# Indome_Ekow_Annan_3031820.net
KiCad netlist of a schematic drawn in EAGLE
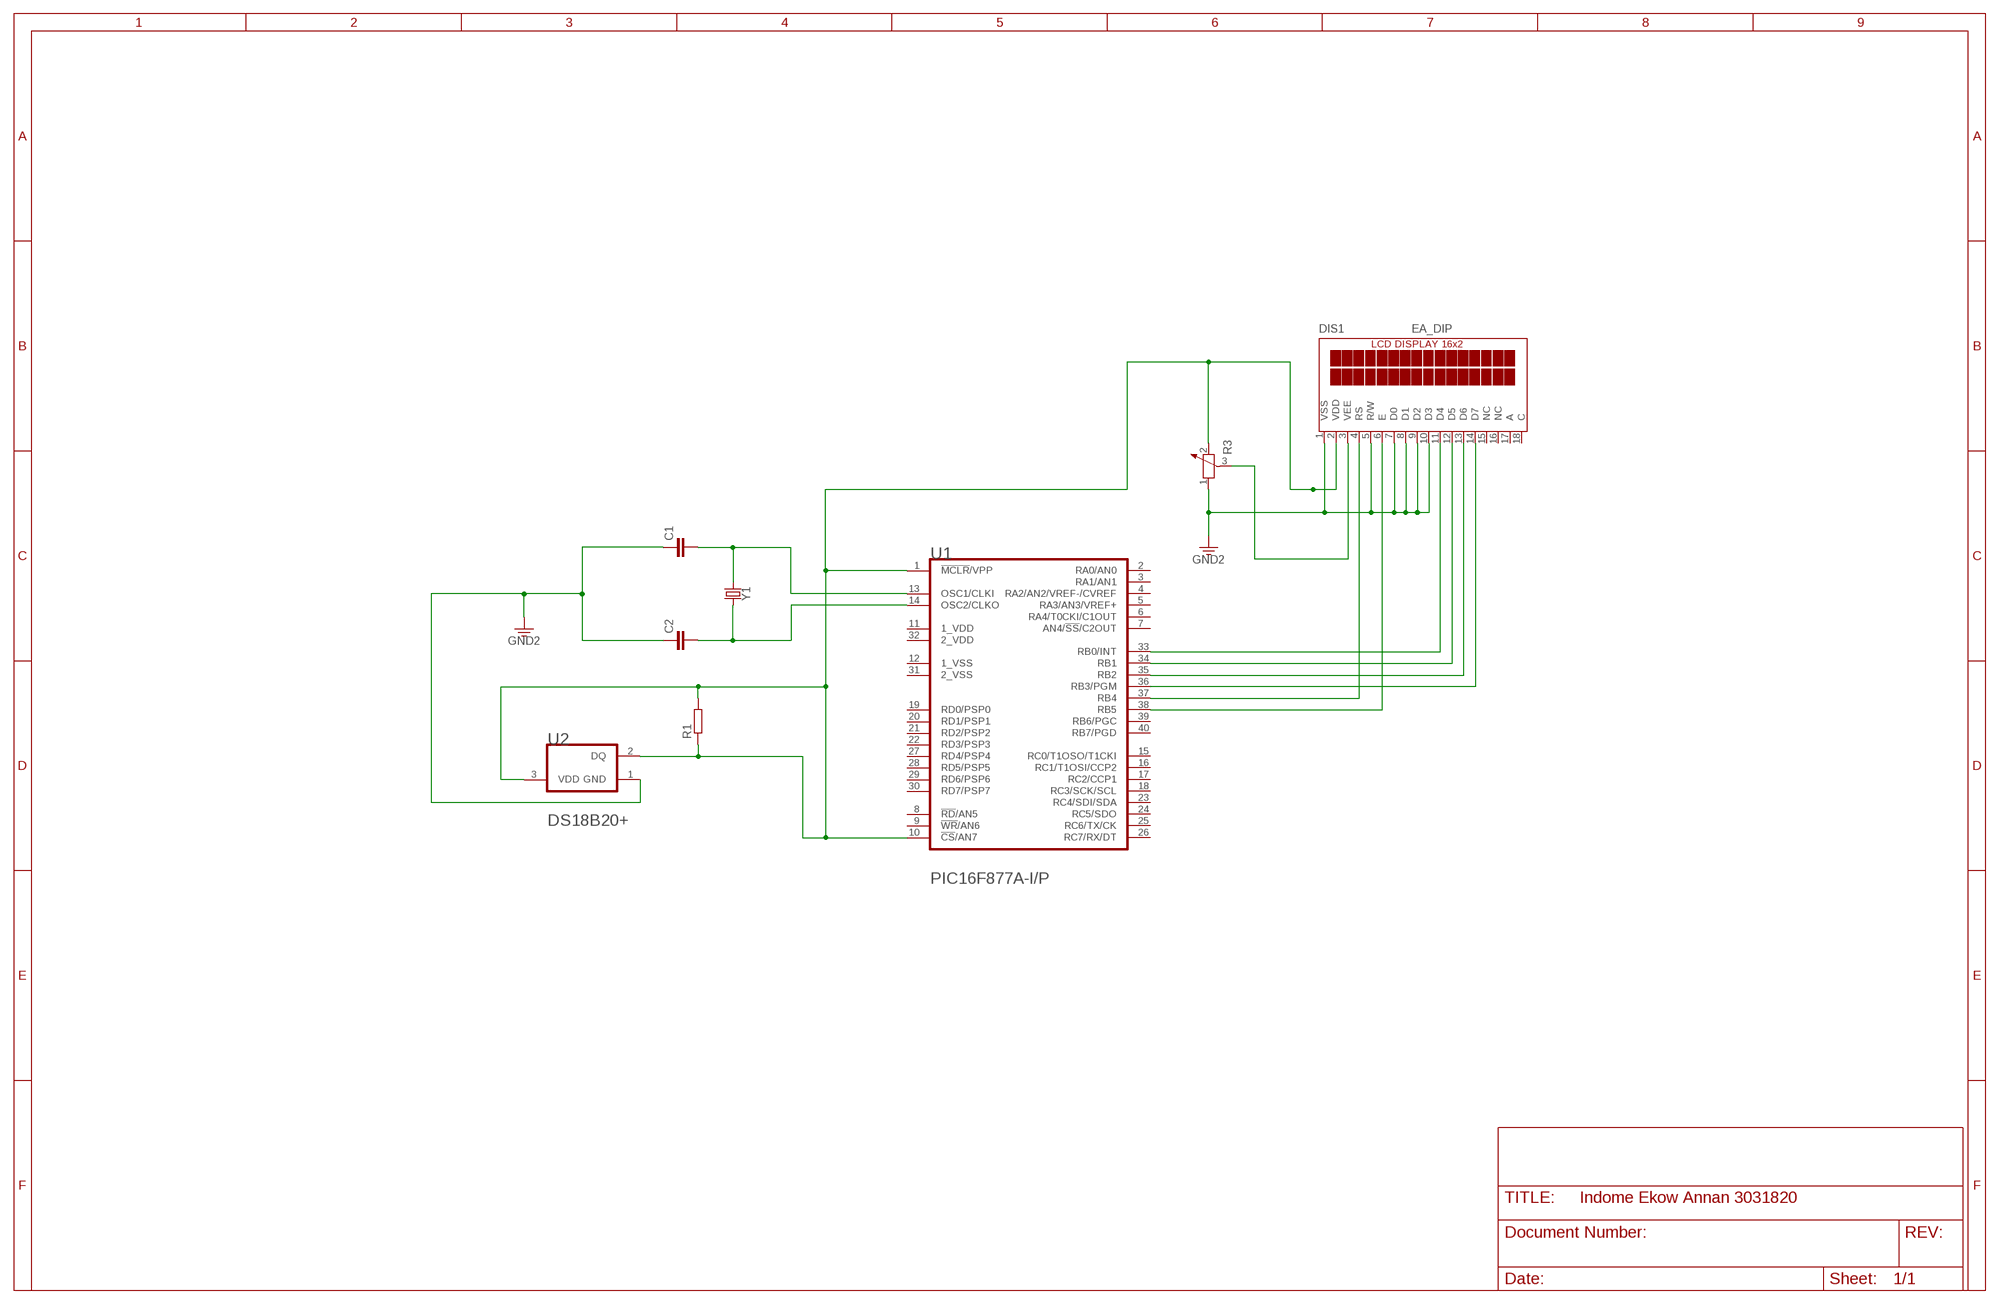
[diagram p0: schematic, sheet 1]

(export (version "E")
  (design (tool "Eeschema 10.0.6"))
  (components
    (comp (ref "C1")
      (value "C2,5-3")
      (footprint "eagle-import:C2.5-3")
      (libsource (lib "eagle-import") (part "C2,5-3"))
    )
    (comp (ref "C2")
      (value "C2,5-3")
      (footprint "eagle-import:C2.5-3")
      (libsource (lib "eagle-import") (part "C2,5-3"))
    )
    (comp (ref "DIS1")
      (value "EA_DIP")
      (footprint "eagle-import:EA_DIP")
      (libsource (lib "eagle-import") (part "EA_DIP"))
    )
    (comp (ref "R1")
      (value "R-EU_0204/2V")
      (footprint "eagle-import:0204V")
      (libsource (lib "eagle-import") (part "R-EU_0204/2V"))
    )
    (comp (ref "R3")
      (value "POTENTIOMETER_PT-10")
      (footprint "eagle-import:PT-10")
      (libsource (lib "eagle-import") (part "POTENTIOMETER_PT-10"))
    )
    (comp (ref "U1")
      (value "MICROCHIP_PIC16F877A-I-PMICROCHIP_PIC16F877A-I-P_0_0")
      (footprint "eagle-import:MICROCHIP_PIC16F877A-I-P_0")
      (fields (field (name "MF") "Microchip") (field (name "MPN") "PIC16F877A-I/P"))
      (libsource (lib "eagle-import") (part "MICROCHIP_PIC16F877A-I-PMICROCHIP_PIC16F877A-I-P_0_0"))
    )
    (comp (ref "U2")
      (value "MAXIM_DS18B20+MAXIM_DS18B20+_0_0")
      (footprint "eagle-import:MAXIM_DS18B20+_0")
      (fields (field (name "MF") "Maxim") (field (name "MPN") "DS18B20+"))
      (libsource (lib "eagle-import") (part "MAXIM_DS18B20+MAXIM_DS18B20+_0_0"))
    )
    (comp (ref "Y1")
      (value "CRYSTALPTH-2X6")
      (footprint "eagle-import:CRYSTAL-PTH-2X6-CYL")
      (libsource (lib "eagle-import") (part "CRYSTALPTH-2X6"))
    )
  )
  (nets
    (net (code "1") (name "/1_VDD") (class "Default")
      (node (ref "U1") (pin "11") (pinfunction "1_VDD_11") (pintype "power_in"))
    )
    (net (code "2") (name "/1_VSS") (class "Default")
      (node (ref "U1") (pin "12") (pinfunction "1_VSS_12") (pintype "power_in"))
    )
    (net (code "3") (name "/2_VDD") (class "Default")
      (node (ref "U1") (pin "32") (pinfunction "2_VDD_32") (pintype "power_in"))
    )
    (net (code "4") (name "/2_VSS") (class "Default")
      (node (ref "U1") (pin "31") (pinfunction "2_VSS_31") (pintype "power_in"))
    )
    (net (code "5") (name "GND2") (class "Default")
      (node (ref "C1") (pin "1") (pinfunction "1_1") (pintype "passive"))
      (node (ref "C2") (pin "1") (pinfunction "1_1") (pintype "passive"))
      (node (ref "DIS1") (pin "1") (pinfunction "VSS_1") (pintype "power_in"))
      (node (ref "DIS1") (pin "10") (pinfunction "D3_10") (pintype "input"))
      (node (ref "DIS1") (pin "5") (pinfunction "R/W_5") (pintype "input"))
      (node (ref "DIS1") (pin "7") (pinfunction "D0_7") (pintype "input"))
      (node (ref "DIS1") (pin "8") (pinfunction "D1_8") (pintype "input"))
      (node (ref "DIS1") (pin "9") (pinfunction "D2_9") (pintype "input"))
      (node (ref "R3") (pin "1") (pinfunction "1_1") (pintype "passive"))
      (node (ref "U2") (pin "1") (pinfunction "GND_1") (pintype "bidirectional"))
    )
    (net (code "6") (name "Net-(DIS1-D4)") (class "Default")
      (node (ref "DIS1") (pin "11") (pinfunction "D4_11") (pintype "input"))
      (node (ref "U1") (pin "33") (pinfunction "RB0/INT_33") (pintype "bidirectional"))
    )
    (net (code "7") (name "Net-(DIS1-D5)") (class "Default")
      (node (ref "DIS1") (pin "12") (pinfunction "D5_12") (pintype "input"))
      (node (ref "U1") (pin "34") (pinfunction "RB1_34") (pintype "bidirectional"))
    )
    (net (code "8") (name "Net-(DIS1-D6)") (class "Default")
      (node (ref "DIS1") (pin "13") (pinfunction "D6_13") (pintype "input"))
      (node (ref "U1") (pin "35") (pinfunction "RB2_35") (pintype "bidirectional"))
    )
    (net (code "9") (name "Net-(DIS1-D7)") (class "Default")
      (node (ref "DIS1") (pin "14") (pinfunction "D7_14") (pintype "input"))
      (node (ref "U1") (pin "36") (pinfunction "RB3/PGM_36") (pintype "bidirectional"))
    )
    (net (code "10") (name "Net-(DIS1-E)") (class "Default")
      (node (ref "DIS1") (pin "6") (pinfunction "E_6") (pintype "input"))
      (node (ref "U1") (pin "38") (pinfunction "RB5_38") (pintype "bidirectional"))
    )
    (net (code "11") (name "Net-(DIS1-RS)") (class "Default")
      (node (ref "DIS1") (pin "4") (pinfunction "RS_4") (pintype "input"))
      (node (ref "U1") (pin "37") (pinfunction "RB4_37") (pintype "bidirectional"))
    )
    (net (code "12") (name "Net-(DIS1-VDD)") (class "Default")
      (node (ref "DIS1") (pin "2") (pinfunction "VDD_2") (pintype "power_in"))
      (node (ref "R1") (pin "1") (pinfunction "1_1") (pintype "passive"))
      (node (ref "R1") (pin "2") (pinfunction "2_2") (pintype "passive"))
      (node (ref "R3") (pin "2") (pinfunction "2_2") (pintype "passive"))
      (node (ref "U1") (pin "1") (pinfunction "~{MCLR}/VPP_1") (pintype "input"))
      (node (ref "U1") (pin "10") (pinfunction "~{CS}/AN7_10") (pintype "bidirectional"))
      (node (ref "U2") (pin "2") (pinfunction "DQ_2") (pintype "bidirectional"))
      (node (ref "U2") (pin "3") (pinfunction "VDD_3") (pintype "bidirectional"))
    )
    (net (code "13") (name "Net-(DIS1-VEE)") (class "Default")
      (node (ref "DIS1") (pin "3") (pinfunction "VEE_3") (pintype "power_in"))
      (node (ref "R3") (pin "3") (pinfunction "3_3") (pintype "passive"))
    )
    (net (code "14") (name "Net-(U1-OSC1{slash}CLKI)") (class "Default")
      (node (ref "C1") (pin "2") (pinfunction "2_2") (pintype "passive"))
      (node (ref "U1") (pin "13") (pinfunction "OSC1/CLKI_13") (pintype "input"))
      (node (ref "Y1") (pin "1") (pinfunction "1_1") (pintype "passive"))
    )
    (net (code "15") (name "Net-(U1-OSC2{slash}CLKO)") (class "Default")
      (node (ref "C2") (pin "2") (pinfunction "2_2") (pintype "passive"))
      (node (ref "U1") (pin "14") (pinfunction "OSC2/CLKO_14") (pintype "output"))
      (node (ref "Y1") (pin "2") (pinfunction "2_2") (pintype "passive"))
    )
    (net (code "16") (name "unconnected-(DIS1-A-Pad17)") (class "Default")
      (node (ref "DIS1") (pin "17") (pinfunction "A_17") (pintype "passive"))
    )
    (net (code "17") (name "unconnected-(DIS1-C-Pad18)") (class "Default")
      (node (ref "DIS1") (pin "18") (pinfunction "C_18") (pintype "passive"))
    )
    (net (code "18") (name "unconnected-(DIS1-NC-Pad15)") (class "Default")
      (node (ref "DIS1") (pin "15") (pinfunction "NC_15") (pintype "no_connect"))
    )
    (net (code "19") (name "unconnected-(DIS1-NC-Pad16)") (class "Default")
      (node (ref "DIS1") (pin "16") (pinfunction "NC_16") (pintype "no_connect"))
    )
    (net (code "20") (name "unconnected-(U1-AN4{slash}~{SS}{slash}C2OUT-Pad7)") (class "Default")
      (node (ref "U1") (pin "7") (pinfunction "AN4/~{SS}/C2OUT_7") (pintype "bidirectional"))
    )
    (net (code "21") (name "unconnected-(U1-RA0{slash}AN0-Pad2)") (class "Default")
      (node (ref "U1") (pin "2") (pinfunction "RA0/AN0_2") (pintype "bidirectional"))
    )
    (net (code "22") (name "unconnected-(U1-RA1{slash}AN1-Pad3)") (class "Default")
      (node (ref "U1") (pin "3") (pinfunction "RA1/AN1_3") (pintype "bidirectional"))
    )
    (net (code "23") (name "unconnected-(U1-RA2{slash}AN2{slash}VREF-{slash}CVREF-Pad4)") (class "Default")
      (node (ref "U1") (pin "4") (pinfunction "RA2/AN2/VREF-/CVREF_4") (pintype "bidirectional"))
    )
    (net (code "24") (name "unconnected-(U1-RA3{slash}AN3{slash}VREF+-Pad5)") (class "Default")
      (node (ref "U1") (pin "5") (pinfunction "RA3/AN3/VREF+_5") (pintype "bidirectional"))
    )
    (net (code "25") (name "unconnected-(U1-RA4{slash}T0CKI{slash}C1OUT-Pad6)") (class "Default")
      (node (ref "U1") (pin "6") (pinfunction "RA4/T0CKI/C1OUT_6") (pintype "bidirectional"))
    )
    (net (code "26") (name "unconnected-(U1-RB6{slash}PGC-Pad39)") (class "Default")
      (node (ref "U1") (pin "39") (pinfunction "RB6/PGC_39") (pintype "bidirectional"))
    )
    (net (code "27") (name "unconnected-(U1-RB7{slash}PGD-Pad40)") (class "Default")
      (node (ref "U1") (pin "40") (pinfunction "RB7/PGD_40") (pintype "bidirectional"))
    )
    (net (code "28") (name "unconnected-(U1-RC0{slash}T1OSO{slash}T1CKI-Pad15)") (class "Default")
      (node (ref "U1") (pin "15") (pinfunction "RC0/T1OSO/T1CKI_15") (pintype "bidirectional"))
    )
    (net (code "29") (name "unconnected-(U1-RC1{slash}T1OSI{slash}CCP2-Pad16)") (class "Default")
      (node (ref "U1") (pin "16") (pinfunction "RC1/T1OSI/CCP2_16") (pintype "bidirectional"))
    )
    (net (code "30") (name "unconnected-(U1-RC2{slash}CCP1-Pad17)") (class "Default")
      (node (ref "U1") (pin "17") (pinfunction "RC2/CCP1_17") (pintype "bidirectional"))
    )
    (net (code "31") (name "unconnected-(U1-RC3{slash}SCK{slash}SCL-Pad18)") (class "Default")
      (node (ref "U1") (pin "18") (pinfunction "RC3/SCK/SCL_18") (pintype "bidirectional"))
    )
    (net (code "32") (name "unconnected-(U1-RC4{slash}SDI{slash}SDA-Pad23)") (class "Default")
      (node (ref "U1") (pin "23") (pinfunction "RC4/SDI/SDA_23") (pintype "bidirectional"))
    )
    (net (code "33") (name "unconnected-(U1-RC5{slash}SDO-Pad24)") (class "Default")
      (node (ref "U1") (pin "24") (pinfunction "RC5/SDO_24") (pintype "bidirectional"))
    )
    (net (code "34") (name "unconnected-(U1-RC6{slash}TX{slash}CK-Pad25)") (class "Default")
      (node (ref "U1") (pin "25") (pinfunction "RC6/TX/CK_25") (pintype "bidirectional"))
    )
    (net (code "35") (name "unconnected-(U1-RC7{slash}RX{slash}DT-Pad26)") (class "Default")
      (node (ref "U1") (pin "26") (pinfunction "RC7/RX/DT_26") (pintype "bidirectional"))
    )
    (net (code "36") (name "unconnected-(U1-RD0{slash}PSP0-Pad19)") (class "Default")
      (node (ref "U1") (pin "19") (pinfunction "RD0/PSP0_19") (pintype "bidirectional"))
    )
    (net (code "37") (name "unconnected-(U1-RD1{slash}PSP1-Pad20)") (class "Default")
      (node (ref "U1") (pin "20") (pinfunction "RD1/PSP1_20") (pintype "bidirectional"))
    )
    (net (code "38") (name "unconnected-(U1-RD2{slash}PSP2-Pad21)") (class "Default")
      (node (ref "U1") (pin "21") (pinfunction "RD2/PSP2_21") (pintype "bidirectional"))
    )
    (net (code "39") (name "unconnected-(U1-RD3{slash}PSP3-Pad22)") (class "Default")
      (node (ref "U1") (pin "22") (pinfunction "RD3/PSP3_22") (pintype "bidirectional"))
    )
    (net (code "40") (name "unconnected-(U1-RD4{slash}PSP4-Pad27)") (class "Default")
      (node (ref "U1") (pin "27") (pinfunction "RD4/PSP4_27") (pintype "bidirectional"))
    )
    (net (code "41") (name "unconnected-(U1-RD5{slash}PSP5-Pad28)") (class "Default")
      (node (ref "U1") (pin "28") (pinfunction "RD5/PSP5_28") (pintype "bidirectional"))
    )
    (net (code "42") (name "unconnected-(U1-RD6{slash}PSP6-Pad29)") (class "Default")
      (node (ref "U1") (pin "29") (pinfunction "RD6/PSP6_29") (pintype "bidirectional"))
    )
    (net (code "43") (name "unconnected-(U1-RD7{slash}PSP7-Pad30)") (class "Default")
      (node (ref "U1") (pin "30") (pinfunction "RD7/PSP7_30") (pintype "bidirectional"))
    )
    (net (code "44") (name "unconnected-(U1-~{RD}{slash}AN5-Pad8)") (class "Default")
      (node (ref "U1") (pin "8") (pinfunction "~{RD}/AN5_8") (pintype "bidirectional"))
    )
    (net (code "45") (name "unconnected-(U1-~{WR}{slash}AN6-Pad9)") (class "Default")
      (node (ref "U1") (pin "9") (pinfunction "~{WR}/AN6_9") (pintype "bidirectional"))
    )
  )
)
